# plp-cp_2a.net
KiCad netlist of a schematic drawn in Altium Designer
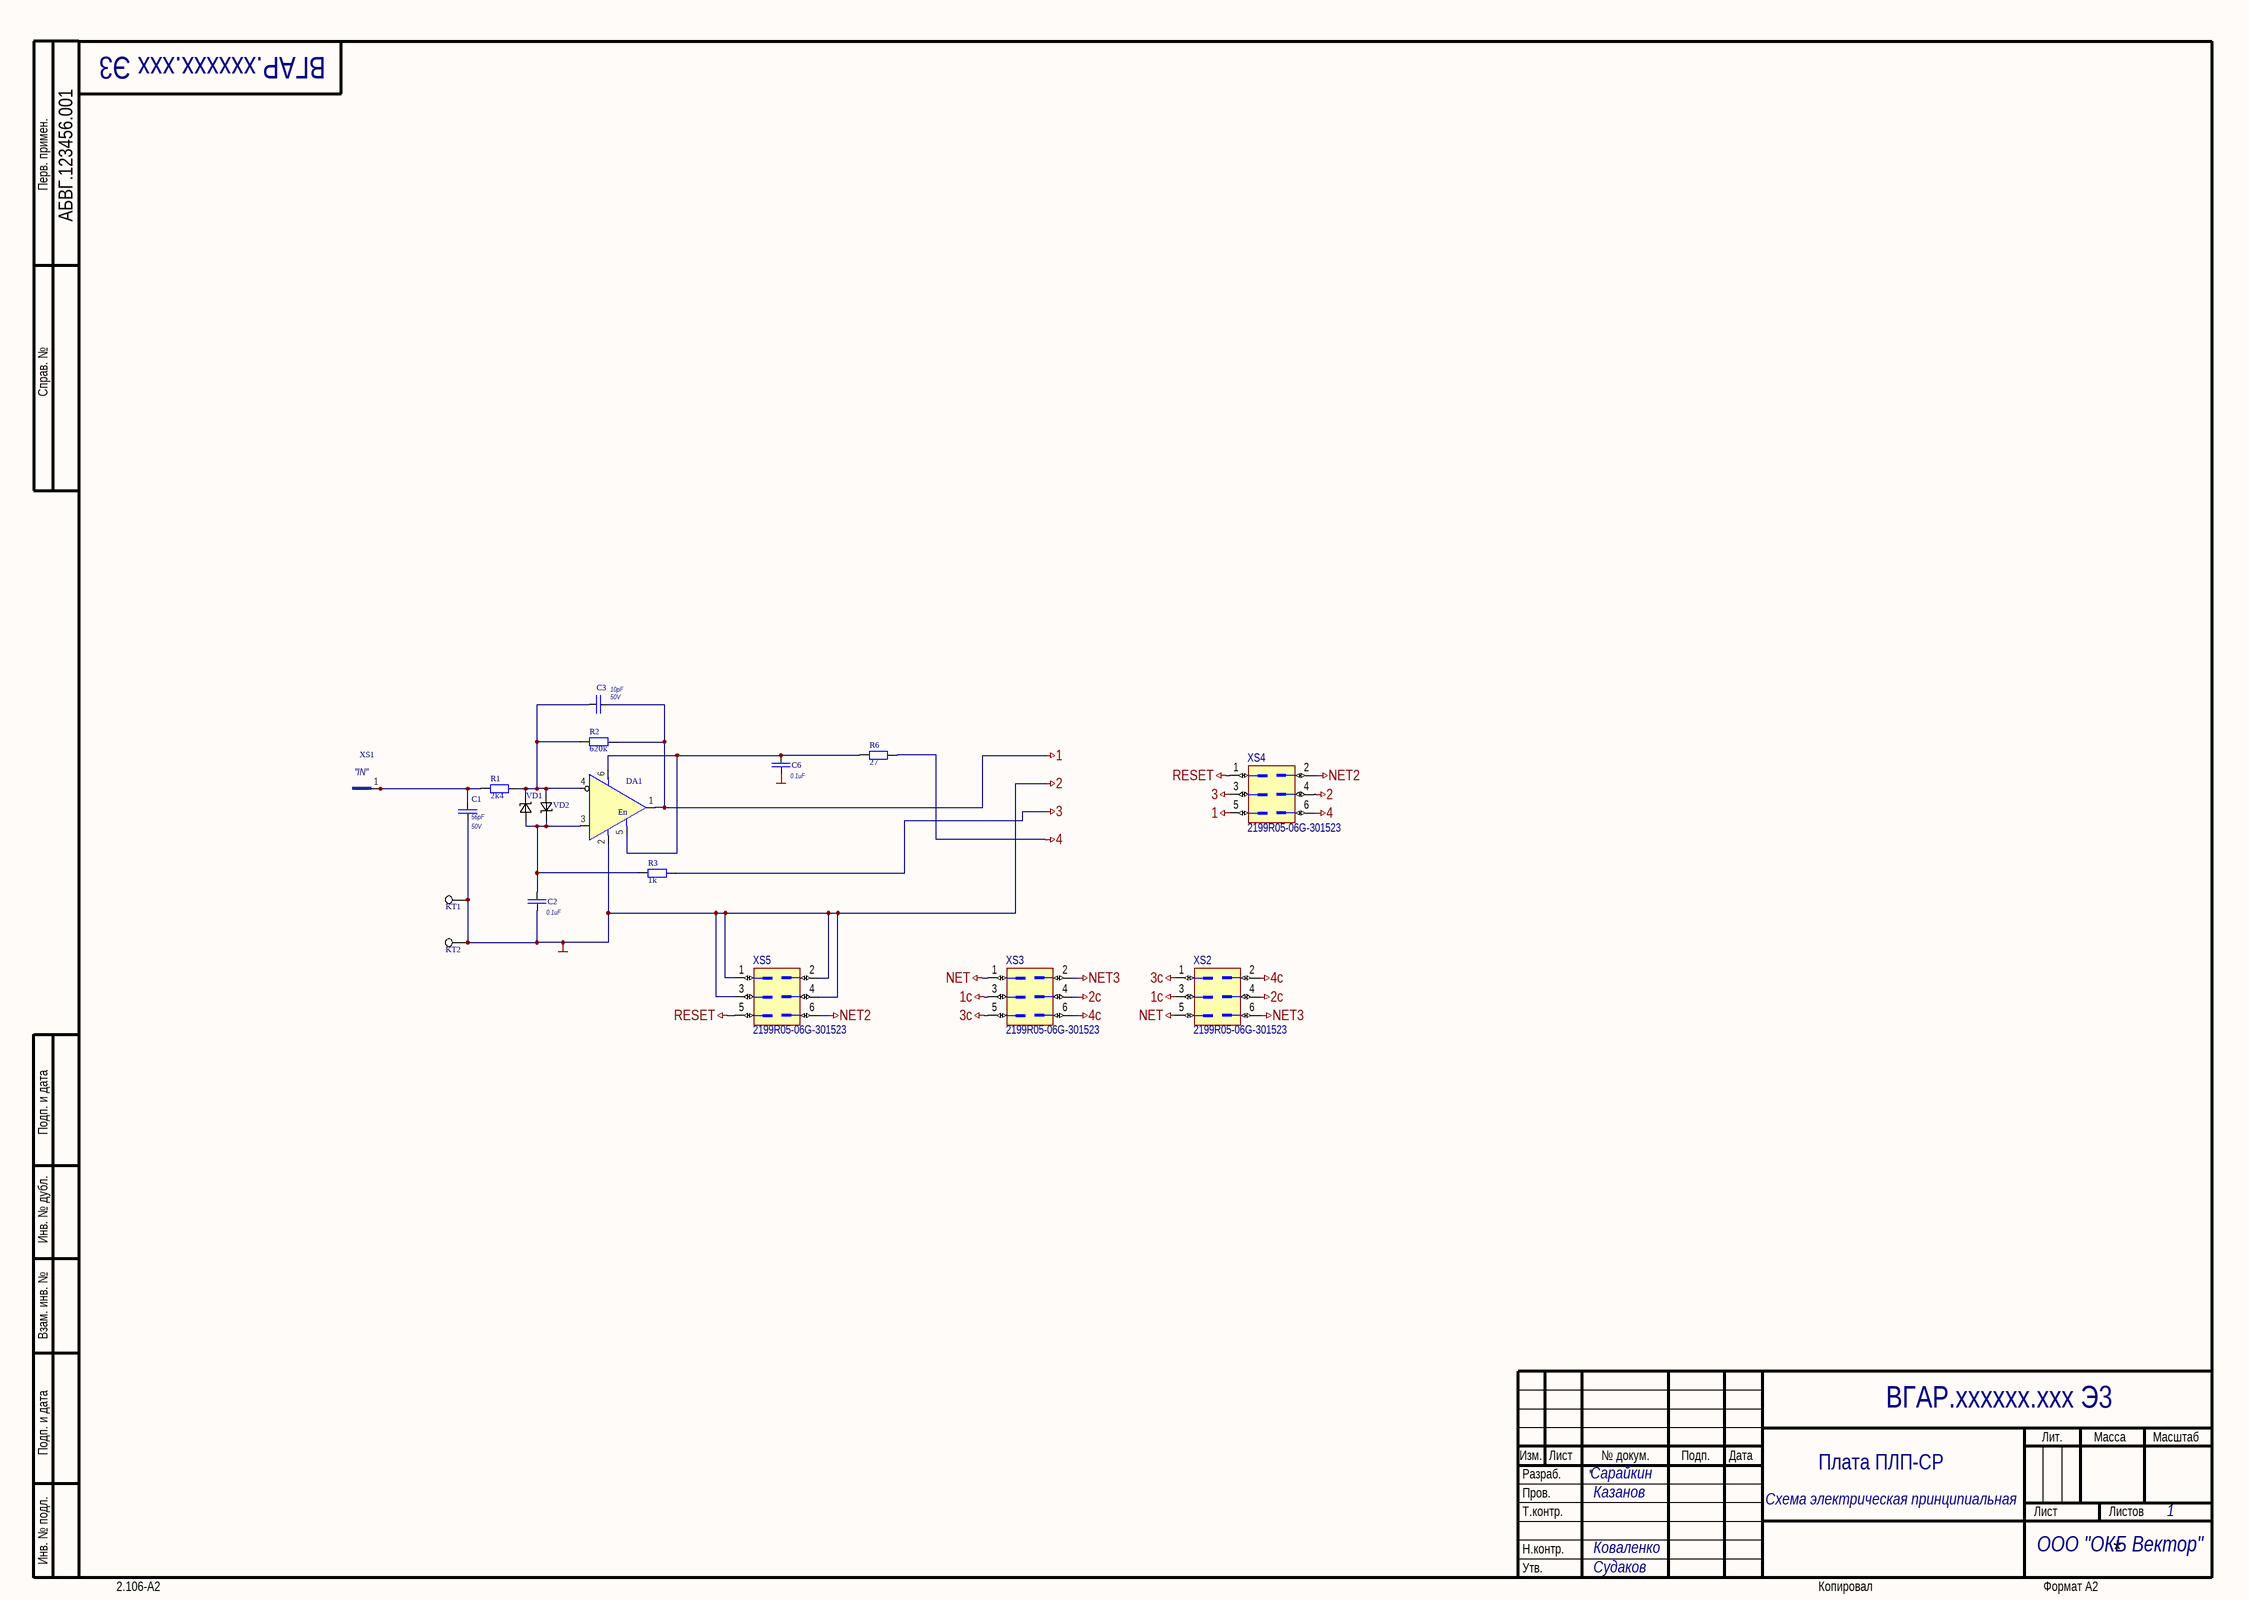
[diagram p0: plp-cp_2a.SchDoc]

(export (version "E")
  (design (tool "Eeschema 10.0.6"))
  (components
    (comp (ref "C1")
      (value "56pF")
      (footprint "CAPC_0603(1608)X080L")
      (description "Конденсатор")
      (fields
        (field (name "MANUFACTURER") "Murata")
        (field (name "TOLERANCE") "±5%")
        (field (name "RATED DC VOLTAGE") "50V")
      )
      (libsource (lib "Chip Capacitor") (part "Capacitor Ceramic"))
    )
    (comp (ref "C2")
      (value "0.1uF")
      (footprint "CAPC_0603(1608)X080L")
      (description "Конденсатор")
      (fields (field (name "MANUFACTURER") "Murata") (field (name "TOLERANCE") "±10%"))
      (libsource (lib "Chip Capacitor") (part "Capacitor Ceramic"))
    )
    (comp (ref "C3")
      (value "10pF")
      (footprint "CAPC_0603(1608)X080L")
      (description "Конденсатор")
      (fields
        (field (name "MANUFACTURER") "Murata")
        (field (name "TOLERANCE") "±5%")
        (field (name "RATED DC VOLTAGE") "50V")
      )
      (libsource (lib "Chip Capacitor") (part "Capacitor Ceramic"))
    )
    (comp (ref "C6")
      (value "0.1uF")
      (footprint "CAPC_0603(1608)X080L")
      (description "Конденсатор")
      (fields (field (name "MANUFACTURER") "Murata") (field (name "TOLERANCE") "±10%"))
      (libsource (lib "Chip Capacitor") (part "Capacitor Ceramic"))
    )
    (comp (ref "DA1")
      (value "OPA363AIDBV")
      (footprint "SOT23-6")
      (description "Микросхема")
      (fields (field (name "MANUFACTURER") "Texas Instruments"))
      (libsource (lib "TI Operational Amplifier") (part "OPA363AIDBV"))
    )
    (comp (ref "KT1")
      (value "Testpoint-TH-1mm")
      (footprint "1mm PAD")
      (description "Dummy Pad")
      (libsource (lib "Board Level Debug Tools") (part "Testpoint-TH-1mm"))
    )
    (comp (ref "KT2")
      (value "Testpoint-TH-1mm")
      (footprint "1mm PAD")
      (description "Dummy Pad")
      (libsource (lib "Board Level Debug Tools") (part "Testpoint-TH-1mm"))
    )
    (comp (ref "R1")
      (value "2k4")
      (footprint "RESC1608(0603)X04L")
      (description "Резистор")
      (fields (field (name "MANUFACTURER") "Bourns") (field (name "POWER") "1/10 Вт"))
      (libsource (lib "Chip Resistor") (part "R0603L"))
    )
    (comp (ref "R2")
      (value "620k")
      (footprint "RESC1608(0603)X04L")
      (description "Резистор")
      (fields (field (name "MANUFACTURER") "Bourns") (field (name "POWER") "1/10 Вт"))
      (libsource (lib "") (part "R0603L_1"))
    )
    (comp (ref "R3")
      (value "1k")
      (footprint "RESC1608(0603)X04L")
      (description "Резистор")
      (fields (field (name "MANUFACTURER") "Bourns") (field (name "POWER") "1/10 Вт"))
      (libsource (lib "") (part "R0603L_1"))
    )
    (comp (ref "R6")
      (value "27")
      (footprint "RESC1608(0603)X04L")
      (description "Резистор")
      (fields (field (name "MANUFACTURER") "Bourns") (field (name "POWER") "1/10 Вт"))
      (libsource (lib "Chip Resistor") (part "R0603L"))
    )
    (comp (ref "VD1")
      (value "BAT54XV2")
      (footprint "SOD523 - ONs")
      (description "shottky diode")
      (fields (field (name "MANUFACTURER") "ON Semiconductor"))
      (libsource (lib "On Semi Diodes") (part "BAT54XV2"))
    )
    (comp (ref "VD2")
      (value "BAT54XV2")
      (footprint "SOD523 - ONs")
      (description "shottky diode")
      (fields (field (name "MANUFACTURER") "ON Semiconductor"))
      (libsource (lib "On Semi Diodes") (part "BAT54XV2"))
    )
    (comp (ref "XS1")
      (value "smd_pin")
      (footprint "smd_pin")
      (libsource (lib "Board Level Debug Tools") (part "smd_pin"))
    )
    (comp (ref "XS2")
      (value "2199R05-06G-301523")
      (footprint "CON: PLL-6(2x3R1.27male)")
      (description "Step 1.27 R")
      (libsource (lib "connector") (part "2199R05-06G-301523Out"))
    )
    (comp (ref "XS3")
      (value "2199R05-06G-301523")
      (footprint "CON: PLL-6(2x3R1.27male)")
      (description "Step 1.27 R")
      (libsource (lib "connector") (part "2199R05-06G-301523Out"))
    )
    (comp (ref "XS4")
      (value "2199R05-06G-301523")
      (footprint "CON: PLL-6(2x3R1.27male)")
      (description "Step 1.27 R")
      (libsource (lib "connector") (part "2199R05-06G-301523Out"))
    )
    (comp (ref "XS5")
      (value "2199R05-06G-301523")
      (footprint "CON: PLL-6(2x3R1.27male)")
      (description "Step 1.27 R")
      (libsource (lib "connector") (part "2199R05-06G-301523Out"))
    )
  )
  (nets
    (net (code "1") (name "1") (class "Default")
      (node (ref "C3") (pin "2") (pinfunction "2_2") (pintype "passive"))
      (node (ref "DA1") (pin "1") (pinfunction "Vout_1") (pintype "passive"))
      (node (ref "R2") (pin "2") (pinfunction "2_2") (pintype "passive"))
      (node (ref "XS4") (pin "5") (pinfunction "5_5") (pintype "bidirectional"))
    )
    (net (code "2") (name "1c") (class "Default")
      (node (ref "XS2") (pin "3") (pinfunction "3_3") (pintype "bidirectional"))
      (node (ref "XS3") (pin "3") (pinfunction "3_3") (pintype "bidirectional"))
    )
    (net (code "3") (name "2") (class "Default")
      (node (ref "C1") (pin "2") (pinfunction "2_2") (pintype "passive"))
      (node (ref "C2") (pin "2") (pinfunction "2_2") (pintype "passive"))
      (node (ref "C6") (pin "2") (pinfunction "2_2") (pintype "passive"))
      (node (ref "DA1") (pin "2") (pinfunction "-V_2") (pintype "passive"))
      (node (ref "KT1") (pin "0") (pinfunction "0_0") (pintype "passive"))
      (node (ref "KT2") (pin "0") (pinfunction "0_0") (pintype "passive"))
      (node (ref "XS4") (pin "4") (pinfunction "4_4") (pintype "bidirectional"))
      (node (ref "XS5") (pin "1") (pinfunction "1_1") (pintype "bidirectional"))
      (node (ref "XS5") (pin "2") (pinfunction "2_2") (pintype "bidirectional"))
      (node (ref "XS5") (pin "3") (pinfunction "3_3") (pintype "bidirectional"))
      (node (ref "XS5") (pin "4") (pinfunction "4_4") (pintype "bidirectional"))
    )
    (net (code "4") (name "2c") (class "Default")
      (node (ref "XS2") (pin "4") (pinfunction "4_4") (pintype "bidirectional"))
      (node (ref "XS3") (pin "4") (pinfunction "4_4") (pintype "bidirectional"))
    )
    (net (code "5") (name "3") (class "Default")
      (node (ref "R3") (pin "2") (pinfunction "2_2") (pintype "passive"))
      (node (ref "XS4") (pin "3") (pinfunction "3_3") (pintype "bidirectional"))
    )
    (net (code "6") (name "3c") (class "Default")
      (node (ref "XS2") (pin "1") (pinfunction "1_1") (pintype "bidirectional"))
      (node (ref "XS3") (pin "5") (pinfunction "5_5") (pintype "bidirectional"))
    )
    (net (code "7") (name "4") (class "Default")
      (node (ref "R6") (pin "1") (pinfunction "1_1") (pintype "passive"))
      (node (ref "XS4") (pin "6") (pinfunction "6_6") (pintype "bidirectional"))
    )
    (net (code "8") (name "4c") (class "Default")
      (node (ref "XS2") (pin "2") (pinfunction "2_2") (pintype "bidirectional"))
      (node (ref "XS3") (pin "6") (pinfunction "6_6") (pintype "bidirectional"))
    )
    (net (code "9") (name "NET") (class "Default")
      (node (ref "XS2") (pin "5") (pinfunction "5_5") (pintype "bidirectional"))
      (node (ref "XS3") (pin "1") (pinfunction "1_1") (pintype "bidirectional"))
    )
    (net (code "10") (name "NET2") (class "Default")
      (node (ref "XS4") (pin "2") (pinfunction "2_2") (pintype "bidirectional"))
      (node (ref "XS5") (pin "6") (pinfunction "6_6") (pintype "bidirectional"))
    )
    (net (code "11") (name "NET3") (class "Default")
      (node (ref "XS2") (pin "6") (pinfunction "6_6") (pintype "bidirectional"))
      (node (ref "XS3") (pin "2") (pinfunction "2_2") (pintype "bidirectional"))
    )
    (net (code "12") (name "Net-(DA1-+In)") (class "Default")
      (node (ref "C2") (pin "1") (pinfunction "1_1") (pintype "passive"))
      (node (ref "DA1") (pin "3") (pinfunction "+In_3") (pintype "passive"))
      (node (ref "R3") (pin "1") (pinfunction "1_1") (pintype "passive"))
      (node (ref "VD1") (pin "1") (pinfunction "anode_1") (pintype "passive"))
      (node (ref "VD2") (pin "2") (pinfunction "catode_2") (pintype "passive"))
    )
    (net (code "13") (name "Net-(DA1-+V)") (class "Default")
      (node (ref "C6") (pin "1") (pinfunction "1_1") (pintype "passive"))
      (node (ref "DA1") (pin "5") (pinfunction "EN_5") (pintype "passive"))
      (node (ref "DA1") (pin "6") (pinfunction "+V_6") (pintype "passive"))
      (node (ref "R6") (pin "2") (pinfunction "2_2") (pintype "passive"))
    )
    (net (code "14") (name "Net-(DA1--In)") (class "Default")
      (node (ref "C3") (pin "1") (pinfunction "1_1") (pintype "passive"))
      (node (ref "DA1") (pin "4") (pinfunction "-In_4") (pintype "passive"))
      (node (ref "R1") (pin "1") (pinfunction "1_1") (pintype "passive"))
      (node (ref "R2") (pin "1") (pinfunction "1_1") (pintype "passive"))
      (node (ref "VD1") (pin "2") (pinfunction "catode_2") (pintype "passive"))
      (node (ref "VD2") (pin "1") (pinfunction "anode_1") (pintype "passive"))
    )
    (net (code "15") (name "Net-(XS1-0)") (class "Default")
      (node (ref "C1") (pin "1") (pinfunction "1_1") (pintype "passive"))
      (node (ref "R1") (pin "2") (pinfunction "2_2") (pintype "passive"))
      (node (ref "XS1") (pin "1") (pinfunction "0_1") (pintype "passive"))
    )
    (net (code "16") (name "RESET") (class "Default")
      (node (ref "XS4") (pin "1") (pinfunction "1_1") (pintype "bidirectional"))
      (node (ref "XS5") (pin "5") (pinfunction "5_5") (pintype "bidirectional"))
    )
  )
)
